# TinyDrop20_V1_1.net
KiCad netlist of a schematic drawn in EAGLE
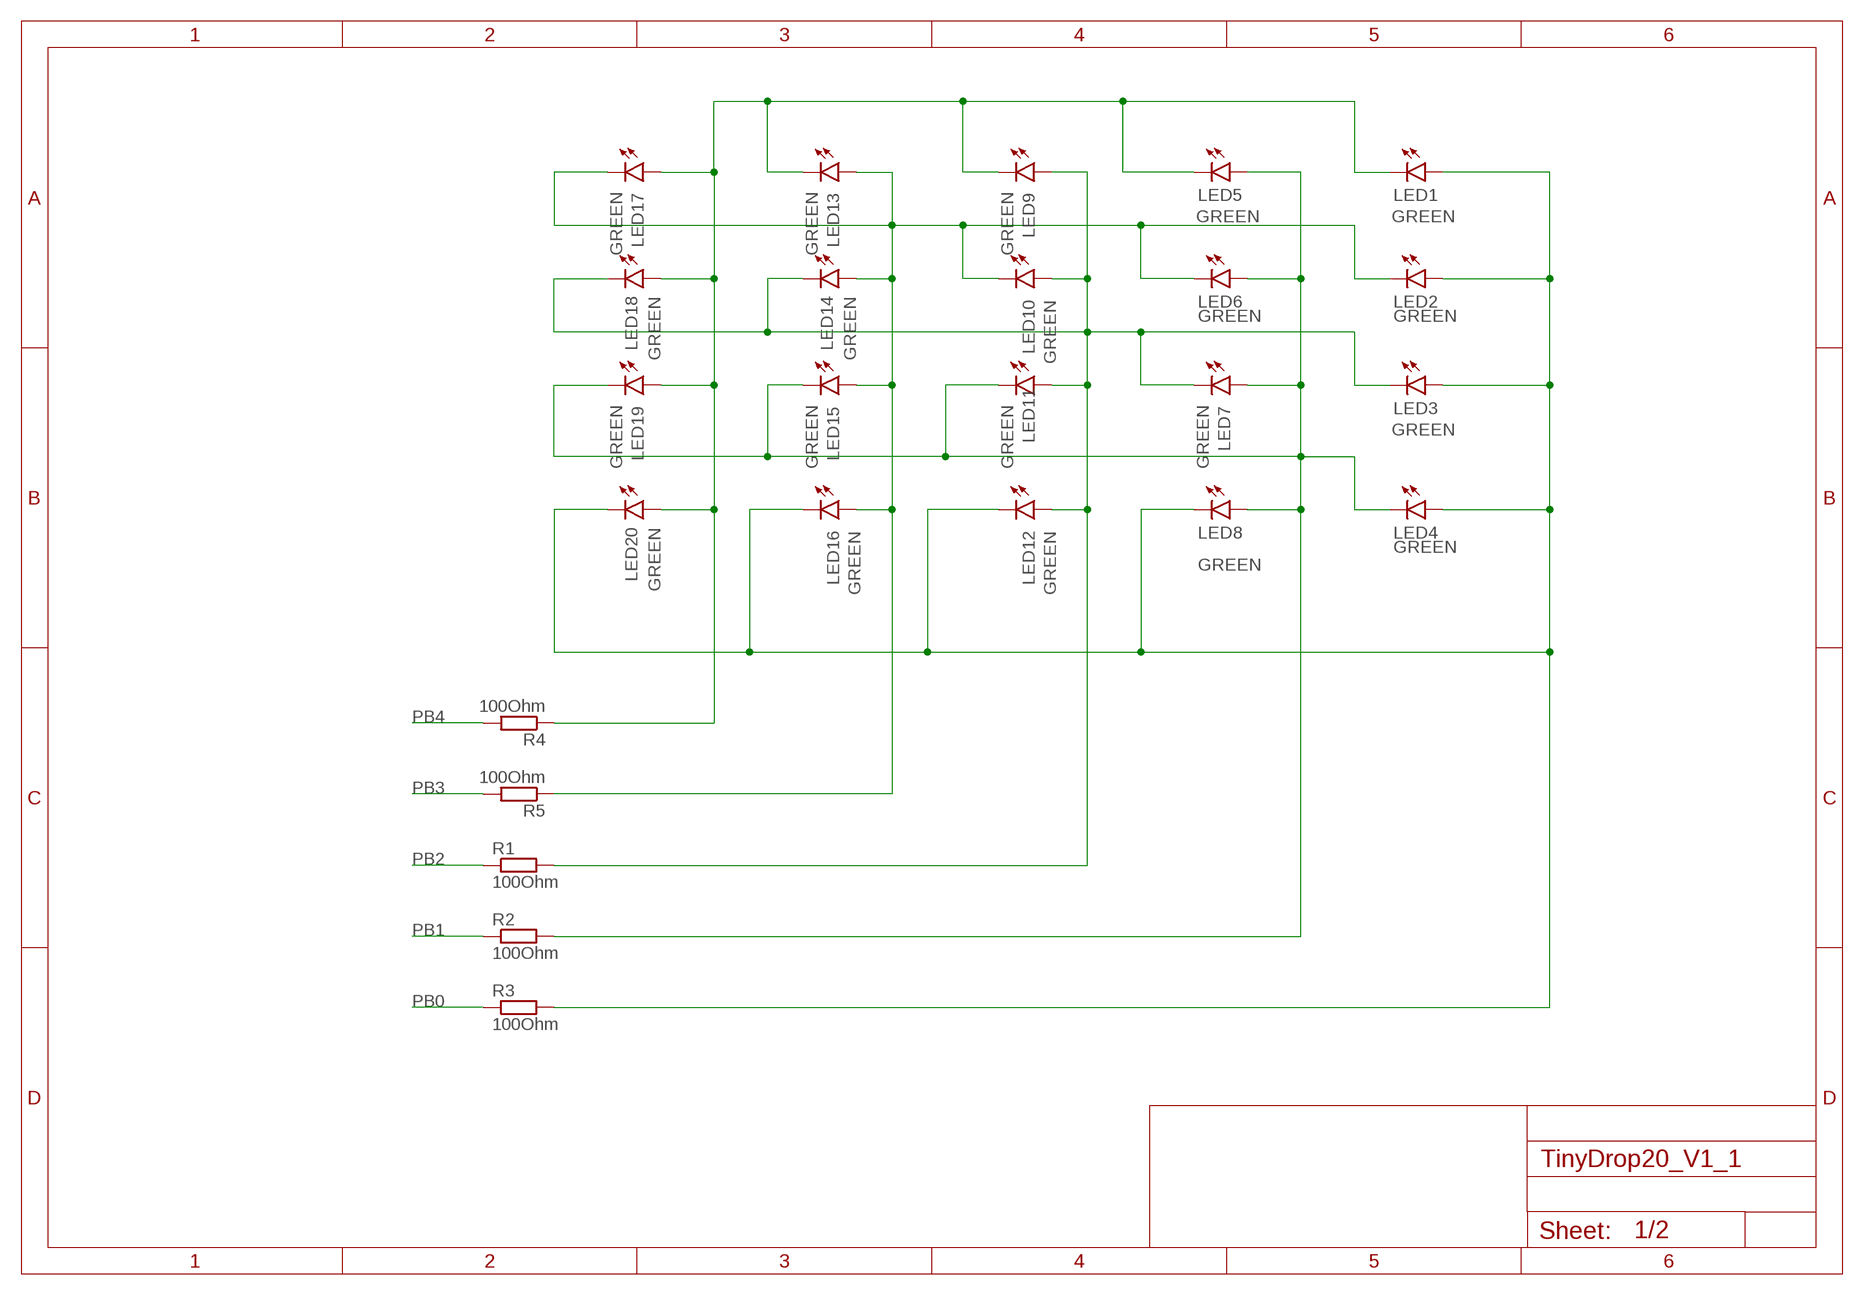
[diagram p0: schematic, sheet 1]
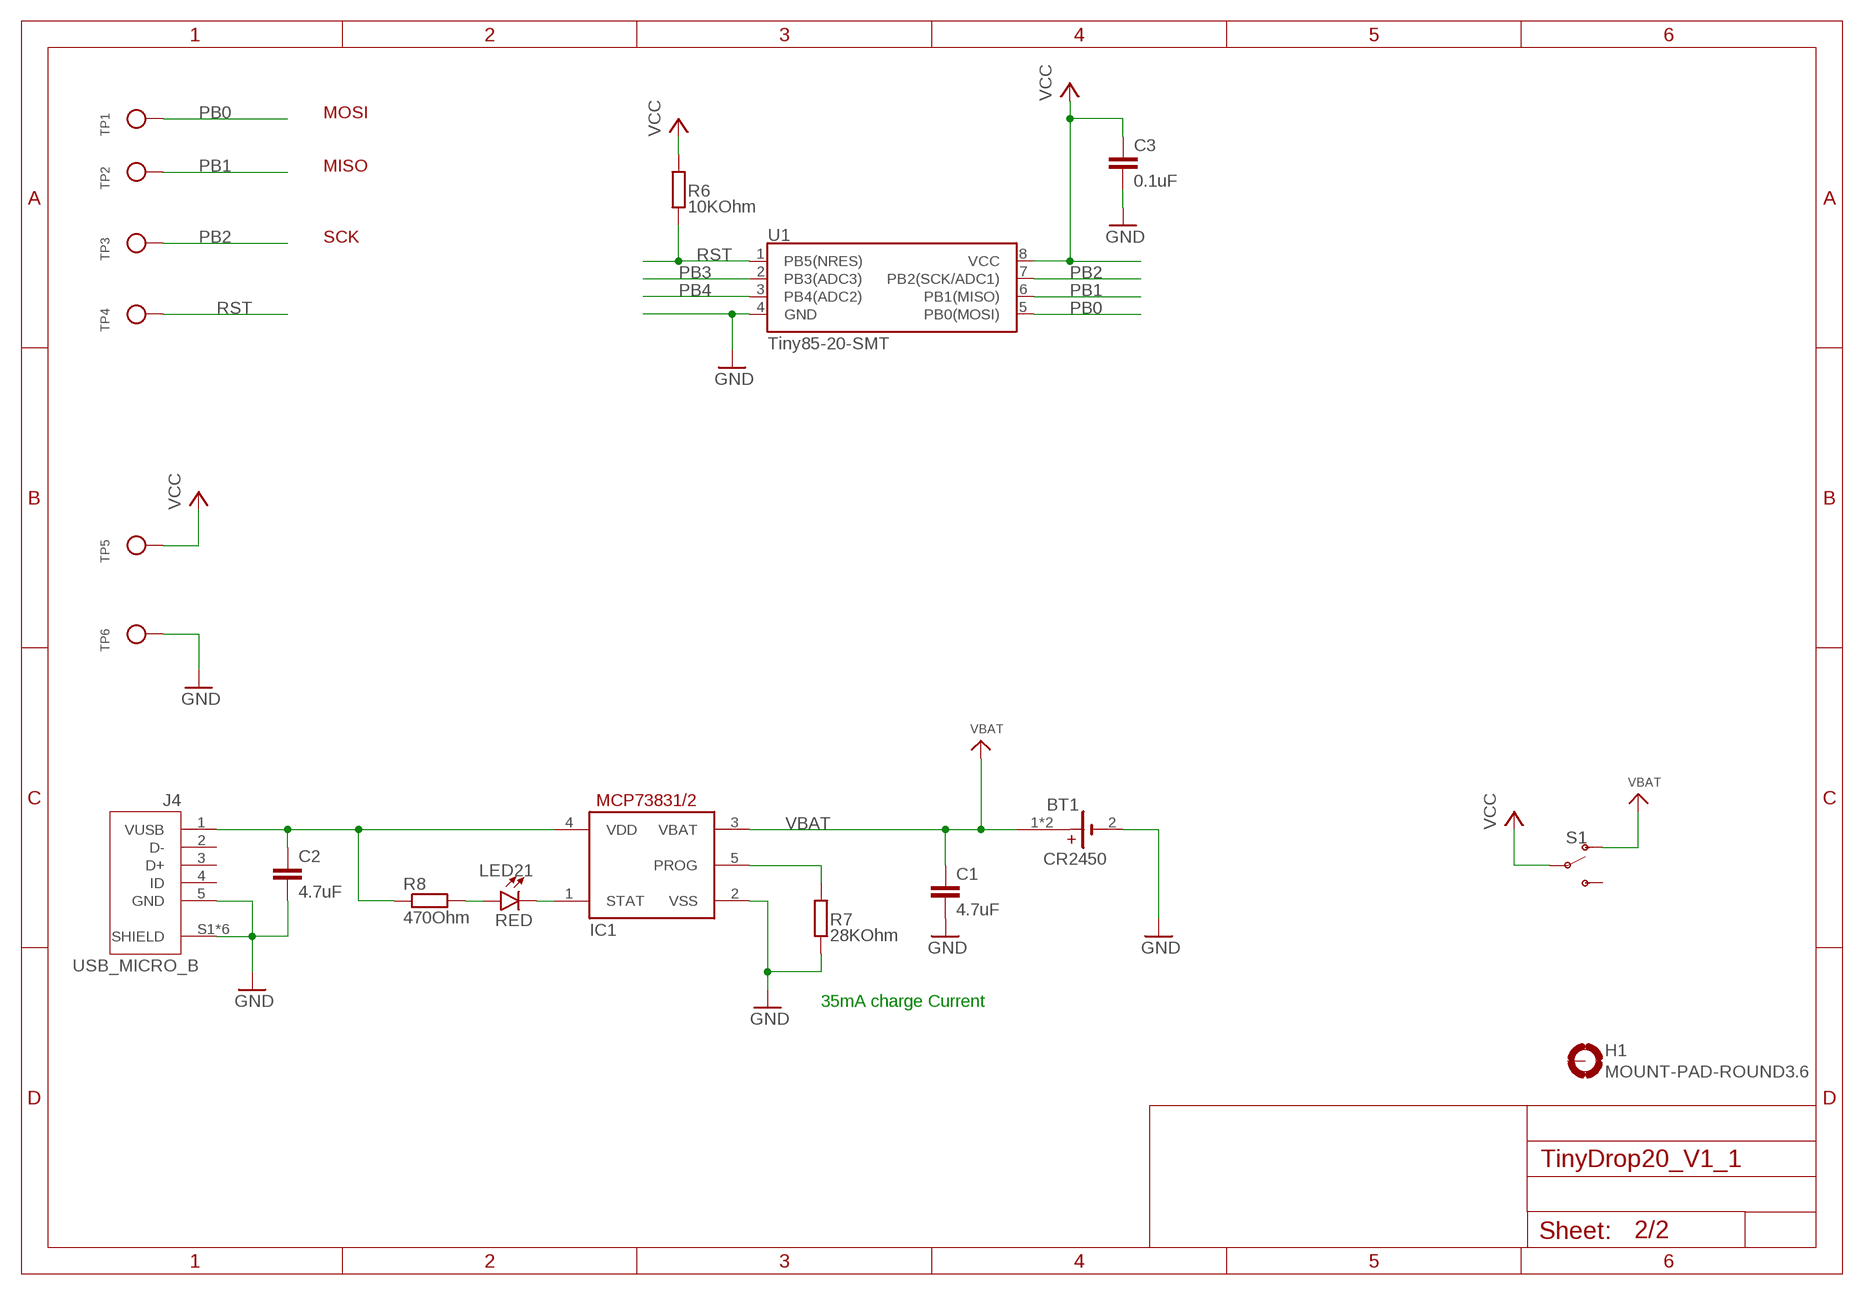
[diagram p1: schematic, sheet 2]

(export (version "E")
  (design (tool "Eeschema 10.0.6"))
  (components
    (comp (ref "BT1")
      (value "CR2450")
      (footprint "eagle-import:BATTCON_24.5X5MM_SMD")
      (libsource (lib "eagle-import") (part "BAT_HOLDER_CR2450"))
    )
    (comp (ref "C1")
      (value "4.7uF")
      (footprint "eagle-import:C0805")
      (fields (field (name "MF") "TDK Corporation") (field (name "MPN") "C2012X7R1A475M125AC"))
      (libsource (lib "eagle-import") (part "4.7UF_CERAMIC_CAPCITUOR-0805"))
    )
    (comp (ref "C2")
      (value "4.7uF")
      (footprint "eagle-import:C0805")
      (fields (field (name "MF") "TDK Corporation") (field (name "MPN") "C2012X7R1A475M125AC"))
      (libsource (lib "eagle-import") (part "4.7UF_CERAMIC_CAPCITUOR-0805"))
    )
    (comp (ref "C3")
      (value "0.1uF")
      (footprint "eagle-import:C0805")
      (fields (field (name "MF") "Yageo"))
      (libsource (lib "eagle-import") (part "0.1UF_CERAMIC_CAPCITUOR-0805"))
    )
    (comp (ref "H1")
      (value "MOUNT-PAD-ROUND3.6")
      (footprint "eagle-import:3,6-PAD")
      (libsource (lib "eagle-import") (part "MOUNT-PAD-ROUND3.6"))
    )
    (comp (ref "IC1")
      (value "MCP73831/OT")
      (footprint "eagle-import:SOT23-5L")
      (fields (field (name "MF") "Microchip Technology") (field (name "MPN") "MCP73831T-2ACI/OT"))
      (libsource (lib "eagle-import") (part "MCP73831/OT"))
    )
    (comp (ref "J4")
      (value "USB_MICRO_B")
      (footprint "eagle-import:FCI_10118193-0001LF")
      (fields (field (name "MF") "Amphenol ICC") (field (name "MPN") "10118193-0001LF"))
      (libsource (lib "eagle-import") (part "USB_MICRO_B"))
    )
    (comp (ref "LED21")
      (value "RED")
      (footprint "eagle-import:CHIPLED_0603")
      (fields (field (name "MF") "Lite-On Inc.") (field (name "MPN") "LTST-C191KRKT"))
      (libsource (lib "eagle-import") (part "LED_0603_RED"))
    )
    (comp (ref "R6")
      (value "10KOhm")
      (footprint "eagle-import:R0603")
      (fields (field (name "MF") "Yageo") (field (name "MPN") "RC0603FR-0710KL"))
      (libsource (lib "eagle-import") (part "10K_RESISTOR-R0603"))
    )
    (comp (ref "R7")
      (value "28KOhm")
      (footprint "eagle-import:R0603")
      (fields (field (name "MF") "Yageo") (field (name "MPN") "RC0603FR-0728KL"))
      (libsource (lib "eagle-import") (part "28K_RESISTOR-R0603"))
    )
    (comp (ref "R8")
      (value "470Ohm")
      (footprint "eagle-import:R0603")
      (fields (field (name "MF") "Bourns Inc") (field (name "MPN") "CR0603-FX-4700ELF"))
      (libsource (lib "eagle-import") (part "470R_RESISTOR-R0603"))
    )
    (comp (ref "S1")
      (value "SWITCH-SPDT-SMD-RIGHT-ANGLE")
      (footprint "eagle-import:SWITCH_SPST_SMD_A")
      (libsource (lib "eagle-import") (part "SWITCH-SPDT-SMD-RIGHT-ANGLE"))
    )
    (comp (ref "TP1")
      (value "TESTPOINTROUND2MM")
      (footprint "eagle-import:TESTPOINT_ROUND_2MM")
      (libsource (lib "eagle-import") (part "TESTPOINTROUND2MM"))
    )
    (comp (ref "TP2")
      (value "TESTPOINTROUND2MM")
      (footprint "eagle-import:TESTPOINT_ROUND_2MM")
      (libsource (lib "eagle-import") (part "TESTPOINTROUND2MM"))
    )
    (comp (ref "TP3")
      (value "TESTPOINTROUND2MM")
      (footprint "eagle-import:TESTPOINT_ROUND_2MM")
      (libsource (lib "eagle-import") (part "TESTPOINTROUND2MM"))
    )
    (comp (ref "TP4")
      (value "TESTPOINTROUND2MM")
      (footprint "eagle-import:TESTPOINT_ROUND_2MM")
      (libsource (lib "eagle-import") (part "TESTPOINTROUND2MM"))
    )
    (comp (ref "TP5")
      (value "TESTPOINTROUND2MM")
      (footprint "eagle-import:TESTPOINT_ROUND_2MM")
      (libsource (lib "eagle-import") (part "TESTPOINTROUND2MM"))
    )
    (comp (ref "TP6")
      (value "TESTPOINTROUND2MM")
      (footprint "eagle-import:TESTPOINT_ROUND_2MM")
      (libsource (lib "eagle-import") (part "TESTPOINTROUND2MM"))
    )
    (comp (ref "U1")
      (value "Tiny85-20-SMT")
      (footprint "eagle-import:SO08-EIAJ_MCU")
      (fields (field (name "MF") "Microchip Technology") (field (name "MPN") "ATTINY85-20SU"))
      (libsource (lib "eagle-import") (part "ATTINY45-TINY85-20-SMT"))
    )
    (comp (ref "LED1")
      (value "GREEN")
      (footprint "eagle-import:CHIPLED_0603")
      (fields (field (name "MF") "Lite-On Inc.") (field (name "MPN") "LTST-C190KGKT"))
      (libsource (lib "eagle-import") (part "LED_0603_GREEN"))
    )
    (comp (ref "LED2")
      (value "GREEN")
      (footprint "eagle-import:CHIPLED_0603")
      (fields (field (name "MF") "Lite-On Inc.") (field (name "MPN") "LTST-C190KGKT"))
      (libsource (lib "eagle-import") (part "LED_0603_GREEN"))
    )
    (comp (ref "LED3")
      (value "GREEN")
      (footprint "eagle-import:CHIPLED_0603")
      (fields (field (name "MF") "Lite-On Inc.") (field (name "MPN") "LTST-C190KGKT"))
      (libsource (lib "eagle-import") (part "LED_0603_GREEN"))
    )
    (comp (ref "LED4")
      (value "GREEN")
      (footprint "eagle-import:CHIPLED_0603")
      (fields (field (name "MF") "Lite-On Inc.") (field (name "MPN") "LTST-C190KGKT"))
      (libsource (lib "eagle-import") (part "LED_0603_GREEN"))
    )
    (comp (ref "LED5")
      (value "GREEN")
      (footprint "eagle-import:CHIPLED_0603")
      (fields (field (name "MF") "Lite-On Inc.") (field (name "MPN") "LTST-C190KGKT"))
      (libsource (lib "eagle-import") (part "LED_0603_GREEN"))
    )
    (comp (ref "LED6")
      (value "GREEN")
      (footprint "eagle-import:CHIPLED_0603")
      (fields (field (name "MF") "Lite-On Inc.") (field (name "MPN") "LTST-C190KGKT"))
      (libsource (lib "eagle-import") (part "LED_0603_GREEN"))
    )
    (comp (ref "LED7")
      (value "GREEN")
      (footprint "eagle-import:CHIPLED_0603")
      (fields (field (name "MF") "Lite-On Inc.") (field (name "MPN") "LTST-C190KGKT"))
      (libsource (lib "eagle-import") (part "LED_0603_GREEN"))
    )
    (comp (ref "LED8")
      (value "GREEN")
      (footprint "eagle-import:CHIPLED_0603")
      (fields (field (name "MF") "Lite-On Inc.") (field (name "MPN") "LTST-C190KGKT"))
      (libsource (lib "eagle-import") (part "LED_0603_GREEN"))
    )
    (comp (ref "LED9")
      (value "GREEN")
      (footprint "eagle-import:CHIPLED_0603")
      (fields (field (name "MF") "Lite-On Inc.") (field (name "MPN") "LTST-C190KGKT"))
      (libsource (lib "eagle-import") (part "LED_0603_GREEN"))
    )
    (comp (ref "LED10")
      (value "GREEN")
      (footprint "eagle-import:CHIPLED_0603")
      (fields (field (name "MF") "Lite-On Inc.") (field (name "MPN") "LTST-C190KGKT"))
      (libsource (lib "eagle-import") (part "LED_0603_GREEN"))
    )
    (comp (ref "LED11")
      (value "GREEN")
      (footprint "eagle-import:CHIPLED_0603")
      (fields (field (name "MF") "Lite-On Inc.") (field (name "MPN") "LTST-C190KGKT"))
      (libsource (lib "eagle-import") (part "LED_0603_GREEN"))
    )
    (comp (ref "LED12")
      (value "GREEN")
      (footprint "eagle-import:CHIPLED_0603")
      (fields (field (name "MF") "Lite-On Inc.") (field (name "MPN") "LTST-C190KGKT"))
      (libsource (lib "eagle-import") (part "LED_0603_GREEN"))
    )
    (comp (ref "LED13")
      (value "GREEN")
      (footprint "eagle-import:CHIPLED_0603")
      (fields (field (name "MF") "Lite-On Inc.") (field (name "MPN") "LTST-C190KGKT"))
      (libsource (lib "eagle-import") (part "LED_0603_GREEN"))
    )
    (comp (ref "LED14")
      (value "GREEN")
      (footprint "eagle-import:CHIPLED_0603")
      (fields (field (name "MF") "Lite-On Inc.") (field (name "MPN") "LTST-C190KGKT"))
      (libsource (lib "eagle-import") (part "LED_0603_GREEN"))
    )
    (comp (ref "LED15")
      (value "GREEN")
      (footprint "eagle-import:CHIPLED_0603")
      (fields (field (name "MF") "Lite-On Inc.") (field (name "MPN") "LTST-C190KGKT"))
      (libsource (lib "eagle-import") (part "LED_0603_GREEN"))
    )
    (comp (ref "LED16")
      (value "GREEN")
      (footprint "eagle-import:CHIPLED_0603")
      (fields (field (name "MF") "Lite-On Inc.") (field (name "MPN") "LTST-C190KGKT"))
      (libsource (lib "eagle-import") (part "LED_0603_GREEN"))
    )
    (comp (ref "LED17")
      (value "GREEN")
      (footprint "eagle-import:CHIPLED_0603")
      (fields (field (name "MF") "Lite-On Inc.") (field (name "MPN") "LTST-C190KGKT"))
      (libsource (lib "eagle-import") (part "LED_0603_GREEN"))
    )
    (comp (ref "LED18")
      (value "GREEN")
      (footprint "eagle-import:CHIPLED_0603")
      (fields (field (name "MF") "Lite-On Inc.") (field (name "MPN") "LTST-C190KGKT"))
      (libsource (lib "eagle-import") (part "LED_0603_GREEN"))
    )
    (comp (ref "LED19")
      (value "GREEN")
      (footprint "eagle-import:CHIPLED_0603")
      (fields (field (name "MF") "Lite-On Inc.") (field (name "MPN") "LTST-C190KGKT"))
      (libsource (lib "eagle-import") (part "LED_0603_GREEN"))
    )
    (comp (ref "LED20")
      (value "GREEN")
      (footprint "eagle-import:CHIPLED_0603")
      (fields (field (name "MF") "Lite-On Inc.") (field (name "MPN") "LTST-C190KGKT"))
      (libsource (lib "eagle-import") (part "LED_0603_GREEN"))
    )
    (comp (ref "R1")
      (value "100Ohm")
      (footprint "eagle-import:R0603")
      (fields (field (name "MF") "Yageo"))
      (libsource (lib "eagle-import") (part "100R_RESISTOR-R0603"))
    )
    (comp (ref "R2")
      (value "100Ohm")
      (footprint "eagle-import:R0603")
      (fields (field (name "MF") "Yageo"))
      (libsource (lib "eagle-import") (part "100R_RESISTOR-R0603"))
    )
    (comp (ref "R3")
      (value "100Ohm")
      (footprint "eagle-import:R0603")
      (fields (field (name "MF") "Yageo"))
      (libsource (lib "eagle-import") (part "100R_RESISTOR-R0603"))
    )
    (comp (ref "R4")
      (value "100Ohm")
      (footprint "eagle-import:R0603")
      (fields (field (name "MF") "Yageo"))
      (libsource (lib "eagle-import") (part "100R_RESISTOR-R0603"))
    )
    (comp (ref "R5")
      (value "100Ohm")
      (footprint "eagle-import:R0603")
      (fields (field (name "MF") "Yageo"))
      (libsource (lib "eagle-import") (part "100R_RESISTOR-R0603"))
    )
  )
  (nets
    (net (code "1") (name "GND") (class "Default")
      (node (ref "BT1") (pin "2") (pinfunction "-_2") (pintype "passive"))
      (node (ref "C1") (pin "2") (pinfunction "2_2") (pintype "passive"))
      (node (ref "C2") (pin "2") (pinfunction "2_2") (pintype "passive"))
      (node (ref "C3") (pin "2") (pinfunction "2_2") (pintype "passive"))
      (node (ref "IC1") (pin "2") (pinfunction "VSS_2") (pintype "power_in"))
      (node (ref "J4") (pin "5") (pinfunction "GND_5") (pintype "passive"))
      (node (ref "J4") (pin "S1") (pinfunction "SHIELD_S1") (pintype "passive"))
      (node (ref "J4") (pin "S2") (pinfunction "SHIELD_S2") (pintype "passive"))
      (node (ref "J4") (pin "S3") (pinfunction "SHIELD_S3") (pintype "passive"))
      (node (ref "J4") (pin "S4") (pinfunction "SHIELD_S4") (pintype "passive"))
      (node (ref "J4") (pin "S5") (pinfunction "SHIELD_S5") (pintype "passive"))
      (node (ref "J4") (pin "S6") (pinfunction "SHIELD_S6") (pintype "passive"))
      (node (ref "R7") (pin "1") (pinfunction "1_1") (pintype "passive"))
      (node (ref "TP6") (pin "P$1") (pinfunction "P$1_P$1") (pintype "bidirectional"))
      (node (ref "U1") (pin "4") (pinfunction "GND_4") (pintype "bidirectional"))
    )
    (net (code "2") (name "Net-(IC1-PROG)") (class "Default")
      (node (ref "IC1") (pin "5") (pinfunction "PROG_5") (pintype "input"))
      (node (ref "R7") (pin "2") (pinfunction "2_2") (pintype "passive"))
    )
    (net (code "3") (name "Net-(IC1-STAT)") (class "Default")
      (node (ref "IC1") (pin "1") (pinfunction "STAT_1") (pintype "output"))
      (node (ref "LED21") (pin "C") (pinfunction "C_C") (pintype "passive"))
    )
    (net (code "4") (name "Net-(IC1-VDD)") (class "Default")
      (node (ref "C2") (pin "1") (pinfunction "1_1") (pintype "passive"))
      (node (ref "IC1") (pin "4") (pinfunction "VDD_4") (pintype "power_in"))
      (node (ref "J4") (pin "1") (pinfunction "VUSB_1") (pintype "passive"))
      (node (ref "R8") (pin "1") (pinfunction "1_1") (pintype "passive"))
    )
    (net (code "5") (name "Net-(LED1-PadA)") (class "Default")
      (node (ref "LED1") (pin "A") (pinfunction "A_A") (pintype "passive"))
      (node (ref "LED12") (pin "C") (pinfunction "C_C") (pintype "passive"))
      (node (ref "LED16") (pin "C") (pinfunction "C_C") (pintype "passive"))
      (node (ref "LED2") (pin "A") (pinfunction "A_A") (pintype "passive"))
      (node (ref "LED20") (pin "C") (pinfunction "C_C") (pintype "passive"))
      (node (ref "LED3") (pin "A") (pinfunction "A_A") (pintype "passive"))
      (node (ref "LED4") (pin "A") (pinfunction "A_A") (pintype "passive"))
      (node (ref "LED8") (pin "C") (pinfunction "C_C") (pintype "passive"))
      (node (ref "R3") (pin "2") (pinfunction "2_2") (pintype "passive"))
    )
    (net (code "6") (name "Net-(LED1-PadC)") (class "Default")
      (node (ref "LED1") (pin "C") (pinfunction "C_C") (pintype "passive"))
      (node (ref "LED13") (pin "C") (pinfunction "C_C") (pintype "passive"))
      (node (ref "LED17") (pin "A") (pinfunction "A_A") (pintype "passive"))
      (node (ref "LED18") (pin "A") (pinfunction "A_A") (pintype "passive"))
      (node (ref "LED19") (pin "A") (pinfunction "A_A") (pintype "passive"))
      (node (ref "LED20") (pin "A") (pinfunction "A_A") (pintype "passive"))
      (node (ref "LED5") (pin "C") (pinfunction "C_C") (pintype "passive"))
      (node (ref "LED9") (pin "C") (pinfunction "C_C") (pintype "passive"))
      (node (ref "R4") (pin "1") (pinfunction "1_1") (pintype "passive"))
    )
    (net (code "7") (name "Net-(LED10-PadA)") (class "Default")
      (node (ref "LED10") (pin "A") (pinfunction "A_A") (pintype "passive"))
      (node (ref "LED11") (pin "A") (pinfunction "A_A") (pintype "passive"))
      (node (ref "LED12") (pin "A") (pinfunction "A_A") (pintype "passive"))
      (node (ref "LED14") (pin "C") (pinfunction "C_C") (pintype "passive"))
      (node (ref "LED18") (pin "C") (pinfunction "C_C") (pintype "passive"))
      (node (ref "LED3") (pin "C") (pinfunction "C_C") (pintype "passive"))
      (node (ref "LED7") (pin "C") (pinfunction "C_C") (pintype "passive"))
      (node (ref "LED9") (pin "A") (pinfunction "A_A") (pintype "passive"))
      (node (ref "R1") (pin "2") (pinfunction "2_2") (pintype "passive"))
    )
    (net (code "8") (name "Net-(LED10-PadC)") (class "Default")
      (node (ref "LED10") (pin "C") (pinfunction "C_C") (pintype "passive"))
      (node (ref "LED13") (pin "A") (pinfunction "A_A") (pintype "passive"))
      (node (ref "LED14") (pin "A") (pinfunction "A_A") (pintype "passive"))
      (node (ref "LED15") (pin "A") (pinfunction "A_A") (pintype "passive"))
      (node (ref "LED16") (pin "A") (pinfunction "A_A") (pintype "passive"))
      (node (ref "LED17") (pin "C") (pinfunction "C_C") (pintype "passive"))
      (node (ref "LED2") (pin "C") (pinfunction "C_C") (pintype "passive"))
      (node (ref "LED6") (pin "C") (pinfunction "C_C") (pintype "passive"))
      (node (ref "R5") (pin "1") (pinfunction "1_1") (pintype "passive"))
    )
    (net (code "9") (name "Net-(LED11-PadC)") (class "Default")
      (node (ref "LED11") (pin "C") (pinfunction "C_C") (pintype "passive"))
      (node (ref "LED15") (pin "C") (pinfunction "C_C") (pintype "passive"))
      (node (ref "LED19") (pin "C") (pinfunction "C_C") (pintype "passive"))
      (node (ref "LED4") (pin "C") (pinfunction "C_C") (pintype "passive"))
      (node (ref "LED5") (pin "A") (pinfunction "A_A") (pintype "passive"))
      (node (ref "LED6") (pin "A") (pinfunction "A_A") (pintype "passive"))
      (node (ref "LED7") (pin "A") (pinfunction "A_A") (pintype "passive"))
      (node (ref "LED8") (pin "A") (pinfunction "A_A") (pintype "passive"))
      (node (ref "R2") (pin "2") (pinfunction "2_2") (pintype "passive"))
    )
    (net (code "10") (name "Net-(LED21-PadA)") (class "Default")
      (node (ref "LED21") (pin "A") (pinfunction "A_A") (pintype "passive"))
      (node (ref "R8") (pin "2") (pinfunction "2_2") (pintype "passive"))
    )
    (net (code "11") (name "PB0") (class "Default")
      (node (ref "R3") (pin "1") (pinfunction "1_1") (pintype "passive"))
      (node (ref "TP1") (pin "P$1") (pinfunction "P$1_P$1") (pintype "bidirectional"))
      (node (ref "U1") (pin "5") (pinfunction "PB0(MOSI)_5") (pintype "bidirectional"))
    )
    (net (code "12") (name "PB1") (class "Default")
      (node (ref "R2") (pin "1") (pinfunction "1_1") (pintype "passive"))
      (node (ref "TP2") (pin "P$1") (pinfunction "P$1_P$1") (pintype "bidirectional"))
      (node (ref "U1") (pin "6") (pinfunction "PB1(MISO)_6") (pintype "bidirectional"))
    )
    (net (code "13") (name "PB2") (class "Default")
      (node (ref "R1") (pin "1") (pinfunction "1_1") (pintype "passive"))
      (node (ref "TP3") (pin "P$1") (pinfunction "P$1_P$1") (pintype "bidirectional"))
      (node (ref "U1") (pin "7") (pinfunction "PB2(SCK/ADC1)_7") (pintype "bidirectional"))
    )
    (net (code "14") (name "PB3") (class "Default")
      (node (ref "R5") (pin "2") (pinfunction "2_2") (pintype "passive"))
      (node (ref "U1") (pin "2") (pinfunction "PB3(ADC3)_2") (pintype "bidirectional"))
    )
    (net (code "15") (name "PB4") (class "Default")
      (node (ref "R4") (pin "2") (pinfunction "2_2") (pintype "passive"))
      (node (ref "U1") (pin "3") (pinfunction "PB4(ADC2)_3") (pintype "bidirectional"))
    )
    (net (code "16") (name "RST") (class "Default")
      (node (ref "R6") (pin "1") (pinfunction "1_1") (pintype "passive"))
      (node (ref "TP4") (pin "P$1") (pinfunction "P$1_P$1") (pintype "bidirectional"))
      (node (ref "U1") (pin "1") (pinfunction "PB5(NRES)_1") (pintype "bidirectional"))
    )
    (net (code "17") (name "VBAT") (class "Default")
      (node (ref "BT1") (pin "1") (pinfunction "+_1") (pintype "passive"))
      (node (ref "BT1") (pin "3") (pinfunction "+_3") (pintype "passive"))
      (node (ref "C1") (pin "1") (pinfunction "1_1") (pintype "passive"))
      (node (ref "IC1") (pin "3") (pinfunction "VBAT_3") (pintype "bidirectional"))
      (node (ref "S1") (pin "1") (pinfunction "O_1") (pintype "passive"))
    )
    (net (code "18") (name "VCC") (class "Default")
      (node (ref "C3") (pin "1") (pinfunction "1_1") (pintype "passive"))
      (node (ref "R6") (pin "2") (pinfunction "2_2") (pintype "passive"))
      (node (ref "S1") (pin "2") (pinfunction "P_2") (pintype "passive"))
      (node (ref "TP5") (pin "P$1") (pinfunction "P$1_P$1") (pintype "bidirectional"))
      (node (ref "U1") (pin "8") (pinfunction "VCC_8") (pintype "bidirectional"))
    )
    (net (code "19") (name "unconnected-(H1-MOUNT-PadB3,6)") (class "Default")
      (node (ref "H1") (pin "B3,6") (pinfunction "MOUNT_B3,6") (pintype "passive"))
    )
    (net (code "20") (name "unconnected-(J4-D+-Pad3)") (class "Default")
      (node (ref "J4") (pin "3") (pinfunction "D+_3") (pintype "passive"))
    )
    (net (code "21") (name "unconnected-(J4-D--Pad2)") (class "Default")
      (node (ref "J4") (pin "2") (pinfunction "D-_2") (pintype "passive"))
    )
    (net (code "22") (name "unconnected-(J4-ID-Pad4)") (class "Default")
      (node (ref "J4") (pin "4") (pinfunction "ID_4") (pintype "passive"))
    )
    (net (code "23") (name "unconnected-(S1-S-Pad3)") (class "Default")
      (node (ref "S1") (pin "3") (pinfunction "S_3") (pintype "passive"))
    )
  )
)
